# balancing_robot_h_bridges_power_sup.net
KiCad netlist of a schematic drawn in EAGLE
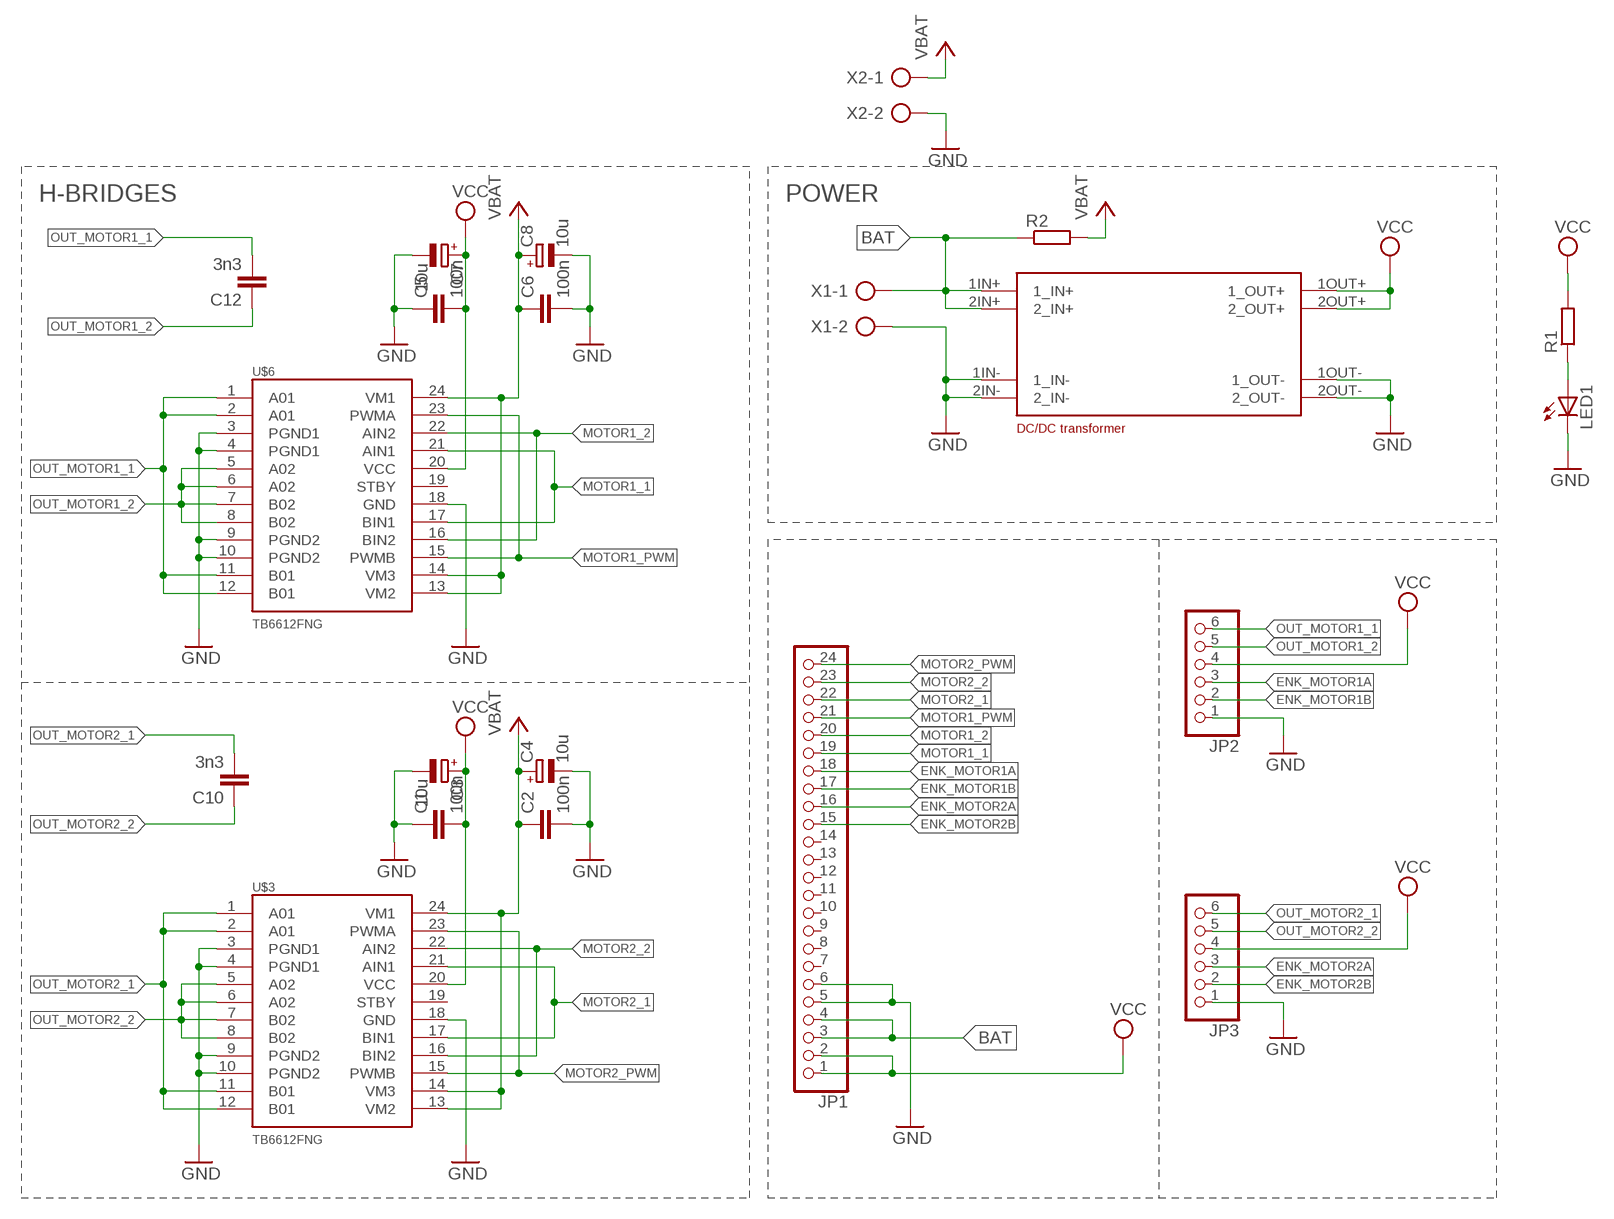
[diagram p0: schematic, sheet 1]

(export (version "E")
  (design (tool "Eeschema 10.0.6"))
  (components
    (comp (ref "C1")
      (value "100n")
      (footprint "eagle-import:C0603")
      (libsource (lib "eagle-import") (part "C-EUC0603"))
    )
    (comp (ref "C2")
      (value "100n")
      (footprint "eagle-import:C0603")
      (libsource (lib "eagle-import") (part "C-EUC0603"))
    )
    (comp (ref "C3")
      (value "10u")
      (footprint "eagle-import:153CLV-0405")
      (libsource (lib "eagle-import") (part "CPOL-EU153CLV-0405"))
    )
    (comp (ref "C4")
      (value "10u")
      (footprint "eagle-import:153CLV-0405")
      (libsource (lib "eagle-import") (part "CPOL-EU153CLV-0405"))
    )
    (comp (ref "C5")
      (value "100n")
      (footprint "eagle-import:C0603")
      (libsource (lib "eagle-import") (part "C-EUC0603"))
    )
    (comp (ref "C6")
      (value "100n")
      (footprint "eagle-import:C0603")
      (libsource (lib "eagle-import") (part "C-EUC0603"))
    )
    (comp (ref "C7")
      (value "10u")
      (footprint "eagle-import:153CLV-0405")
      (libsource (lib "eagle-import") (part "CPOL-EU153CLV-0405"))
    )
    (comp (ref "C8")
      (value "10u")
      (footprint "eagle-import:153CLV-0405")
      (libsource (lib "eagle-import") (part "CPOL-EU153CLV-0405"))
    )
    (comp (ref "C10")
      (value "3n3")
      (footprint "eagle-import:C0603")
      (libsource (lib "eagle-import") (part "C-EUC0603"))
    )
    (comp (ref "C12")
      (value "3n3")
      (footprint "eagle-import:C0603")
      (libsource (lib "eagle-import") (part "C-EUC0603"))
    )
    (comp (ref "JP1")
      (value "PINHD-1X24")
      (footprint "eagle-import:1X24")
      (libsource (lib "eagle-import") (part "PINHD-1X24"))
    )
    (comp (ref "JP2")
      (value "PINHD-1X6")
      (footprint "eagle-import:1X06")
      (libsource (lib "eagle-import") (part "PINHD-1X6"))
    )
    (comp (ref "JP3")
      (value "PINHD-1X6")
      (footprint "eagle-import:1X06")
      (libsource (lib "eagle-import") (part "PINHD-1X6"))
    )
    (comp (ref "LED1")
      (value "LEDCHIP-LED0603")
      (footprint "eagle-import:CHIP-LED0603")
      (libsource (lib "eagle-import") (part "LEDCHIP-LED0603"))
    )
    (comp (ref "R1")
      (value "R-EU_R0603")
      (footprint "eagle-import:R0603")
      (libsource (lib "eagle-import") (part "R-EU_R0603"))
    )
    (comp (ref "R2")
      (value "R-EU_R0805")
      (footprint "eagle-import:R0805")
      (libsource (lib "eagle-import") (part "R-EU_R0805"))
    )
    (comp (ref "U$3")
      (value "TB6612FNG")
      (footprint "eagle-import:SSOP24")
      (libsource (lib "eagle-import") (part "TB6612FNG"))
    )
    (comp (ref "U$4")
      (value "TRANSFORMER")
      (footprint "eagle-import:TRANSFORMER")
      (libsource (lib "eagle-import") (part "TRANSFORMER"))
    )
    (comp (ref "U$6")
      (value "TB6612FNG")
      (footprint "eagle-import:SSOP24")
      (libsource (lib "eagle-import") (part "TB6612FNG"))
    )
    (comp (ref "X1")
      (value "AK500/2")
      (footprint "eagle-import:AK500_2")
      (libsource (lib "eagle-import") (part "AK500/2"))
    )
    (comp (ref "X2")
      (value "AK500/2")
      (footprint "eagle-import:AK500_2")
      (libsource (lib "eagle-import") (part "AK500/2"))
    )
  )
  (nets
    (net (code "1") (name "BAT") (class "Default")
      (node (ref "JP1") (pin "3") (pinfunction "3_3") (pintype "passive"))
      (node (ref "JP1") (pin "4") (pinfunction "4_4") (pintype "passive"))
      (node (ref "R2") (pin "1") (pinfunction "1_1") (pintype "passive"))
      (node (ref "U$4") (pin "1IN+") (pinfunction "1_IN+_1IN+") (pintype "bidirectional"))
      (node (ref "U$4") (pin "2IN+") (pinfunction "2_IN+_2IN+") (pintype "bidirectional"))
      (node (ref "X1") (pin "1") (pinfunction "KL_1") (pintype "passive"))
    )
    (net (code "2") (name "ENK_MOTOR1A") (class "Default")
      (node (ref "JP1") (pin "18") (pinfunction "18_18") (pintype "passive"))
      (node (ref "JP2") (pin "3") (pinfunction "3_3") (pintype "passive"))
    )
    (net (code "3") (name "ENK_MOTOR1B") (class "Default")
      (node (ref "JP1") (pin "17") (pinfunction "17_17") (pintype "passive"))
      (node (ref "JP2") (pin "2") (pinfunction "2_2") (pintype "passive"))
    )
    (net (code "4") (name "ENK_MOTOR2A") (class "Default")
      (node (ref "JP1") (pin "16") (pinfunction "16_16") (pintype "passive"))
      (node (ref "JP3") (pin "3") (pinfunction "3_3") (pintype "passive"))
    )
    (net (code "5") (name "ENK_MOTOR2B") (class "Default")
      (node (ref "JP1") (pin "15") (pinfunction "15_15") (pintype "passive"))
      (node (ref "JP3") (pin "2") (pinfunction "2_2") (pintype "passive"))
    )
    (net (code "6") (name "GND") (class "Default")
      (node (ref "C1") (pin "1") (pinfunction "1_1") (pintype "passive"))
      (node (ref "C2") (pin "2") (pinfunction "2_2") (pintype "passive"))
      (node (ref "C3") (pin "-") (pinfunction "-_-") (pintype "passive"))
      (node (ref "C4") (pin "-") (pinfunction "-_-") (pintype "passive"))
      (node (ref "C5") (pin "1") (pinfunction "1_1") (pintype "passive"))
      (node (ref "C6") (pin "2") (pinfunction "2_2") (pintype "passive"))
      (node (ref "C7") (pin "-") (pinfunction "-_-") (pintype "passive"))
      (node (ref "C8") (pin "-") (pinfunction "-_-") (pintype "passive"))
      (node (ref "JP1") (pin "5") (pinfunction "5_5") (pintype "passive"))
      (node (ref "JP1") (pin "6") (pinfunction "6_6") (pintype "passive"))
      (node (ref "JP2") (pin "1") (pinfunction "1_1") (pintype "passive"))
      (node (ref "JP3") (pin "1") (pinfunction "1_1") (pintype "passive"))
      (node (ref "LED1") (pin "C") (pinfunction "C_C") (pintype "passive"))
      (node (ref "U$3") (pin "10") (pinfunction "PGND2_10") (pintype "bidirectional"))
      (node (ref "U$3") (pin "18") (pinfunction "GND_18") (pintype "bidirectional"))
      (node (ref "U$3") (pin "3") (pinfunction "PGND1_3") (pintype "bidirectional"))
      (node (ref "U$3") (pin "4") (pinfunction "PGND1_4") (pintype "bidirectional"))
      (node (ref "U$3") (pin "9") (pinfunction "PGND2_9") (pintype "bidirectional"))
      (node (ref "U$4") (pin "1IN-") (pinfunction "1_IN-_1IN-") (pintype "bidirectional"))
      (node (ref "U$4") (pin "1OUT-") (pinfunction "1_OUT-_1OUT-") (pintype "bidirectional"))
      (node (ref "U$4") (pin "2IN-") (pinfunction "2_IN-_2IN-") (pintype "bidirectional"))
      (node (ref "U$4") (pin "2OUT-") (pinfunction "2_OUT-_2OUT-") (pintype "bidirectional"))
      (node (ref "U$6") (pin "10") (pinfunction "PGND2_10") (pintype "bidirectional"))
      (node (ref "U$6") (pin "18") (pinfunction "GND_18") (pintype "bidirectional"))
      (node (ref "U$6") (pin "3") (pinfunction "PGND1_3") (pintype "bidirectional"))
      (node (ref "U$6") (pin "4") (pinfunction "PGND1_4") (pintype "bidirectional"))
      (node (ref "U$6") (pin "9") (pinfunction "PGND2_9") (pintype "bidirectional"))
      (node (ref "X1") (pin "2") (pinfunction "KL_2") (pintype "passive"))
      (node (ref "X2") (pin "2") (pinfunction "KL_2") (pintype "passive"))
    )
    (net (code "7") (name "MOTOR1_1") (class "Default")
      (node (ref "JP1") (pin "19") (pinfunction "19_19") (pintype "passive"))
      (node (ref "U$6") (pin "17") (pinfunction "BIN1_17") (pintype "bidirectional"))
      (node (ref "U$6") (pin "21") (pinfunction "AIN1_21") (pintype "bidirectional"))
    )
    (net (code "8") (name "MOTOR1_2") (class "Default")
      (node (ref "JP1") (pin "20") (pinfunction "20_20") (pintype "passive"))
      (node (ref "U$6") (pin "16") (pinfunction "BIN2_16") (pintype "bidirectional"))
      (node (ref "U$6") (pin "22") (pinfunction "AIN2_22") (pintype "bidirectional"))
    )
    (net (code "9") (name "MOTOR1_PWM") (class "Default")
      (node (ref "JP1") (pin "21") (pinfunction "21_21") (pintype "passive"))
      (node (ref "U$6") (pin "15") (pinfunction "PWMB_15") (pintype "bidirectional"))
      (node (ref "U$6") (pin "23") (pinfunction "PWMA_23") (pintype "bidirectional"))
    )
    (net (code "10") (name "MOTOR2_1") (class "Default")
      (node (ref "JP1") (pin "22") (pinfunction "22_22") (pintype "passive"))
      (node (ref "U$3") (pin "17") (pinfunction "BIN1_17") (pintype "bidirectional"))
      (node (ref "U$3") (pin "21") (pinfunction "AIN1_21") (pintype "bidirectional"))
    )
    (net (code "11") (name "MOTOR2_2") (class "Default")
      (node (ref "JP1") (pin "23") (pinfunction "23_23") (pintype "passive"))
      (node (ref "U$3") (pin "16") (pinfunction "BIN2_16") (pintype "bidirectional"))
      (node (ref "U$3") (pin "22") (pinfunction "AIN2_22") (pintype "bidirectional"))
    )
    (net (code "12") (name "MOTOR2_PWM") (class "Default")
      (node (ref "JP1") (pin "24") (pinfunction "24_24") (pintype "passive"))
      (node (ref "U$3") (pin "15") (pinfunction "PWMB_15") (pintype "bidirectional"))
      (node (ref "U$3") (pin "23") (pinfunction "PWMA_23") (pintype "bidirectional"))
    )
    (net (code "13") (name "Net-(LED1-PadA)") (class "Default")
      (node (ref "LED1") (pin "A") (pinfunction "A_A") (pintype "passive"))
      (node (ref "R1") (pin "1") (pinfunction "1_1") (pintype "passive"))
    )
    (net (code "14") (name "OUT_MOTOR1_1") (class "Default")
      (node (ref "C12") (pin "2") (pinfunction "2_2") (pintype "passive"))
      (node (ref "JP2") (pin "6") (pinfunction "6_6") (pintype "passive"))
      (node (ref "U$6") (pin "1") (pinfunction "A01_1") (pintype "bidirectional"))
      (node (ref "U$6") (pin "11") (pinfunction "B01_11") (pintype "bidirectional"))
      (node (ref "U$6") (pin "12") (pinfunction "B01_12") (pintype "bidirectional"))
      (node (ref "U$6") (pin "2") (pinfunction "A01_2") (pintype "bidirectional"))
    )
    (net (code "15") (name "OUT_MOTOR1_2") (class "Default")
      (node (ref "C12") (pin "1") (pinfunction "1_1") (pintype "passive"))
      (node (ref "JP2") (pin "5") (pinfunction "5_5") (pintype "passive"))
      (node (ref "U$6") (pin "5") (pinfunction "A02_5") (pintype "bidirectional"))
      (node (ref "U$6") (pin "6") (pinfunction "A02_6") (pintype "bidirectional"))
      (node (ref "U$6") (pin "7") (pinfunction "B02_7") (pintype "bidirectional"))
      (node (ref "U$6") (pin "8") (pinfunction "B02_8") (pintype "bidirectional"))
    )
    (net (code "16") (name "OUT_MOTOR2_1") (class "Default")
      (node (ref "C10") (pin "2") (pinfunction "2_2") (pintype "passive"))
      (node (ref "JP3") (pin "6") (pinfunction "6_6") (pintype "passive"))
      (node (ref "U$3") (pin "1") (pinfunction "A01_1") (pintype "bidirectional"))
      (node (ref "U$3") (pin "11") (pinfunction "B01_11") (pintype "bidirectional"))
      (node (ref "U$3") (pin "12") (pinfunction "B01_12") (pintype "bidirectional"))
      (node (ref "U$3") (pin "2") (pinfunction "A01_2") (pintype "bidirectional"))
    )
    (net (code "17") (name "OUT_MOTOR2_2") (class "Default")
      (node (ref "C10") (pin "1") (pinfunction "1_1") (pintype "passive"))
      (node (ref "JP3") (pin "5") (pinfunction "5_5") (pintype "passive"))
      (node (ref "U$3") (pin "5") (pinfunction "A02_5") (pintype "bidirectional"))
      (node (ref "U$3") (pin "6") (pinfunction "A02_6") (pintype "bidirectional"))
      (node (ref "U$3") (pin "7") (pinfunction "B02_7") (pintype "bidirectional"))
      (node (ref "U$3") (pin "8") (pinfunction "B02_8") (pintype "bidirectional"))
    )
    (net (code "18") (name "VBAT") (class "Default")
      (node (ref "C1") (pin "2") (pinfunction "2_2") (pintype "passive"))
      (node (ref "C2") (pin "1") (pinfunction "1_1") (pintype "passive"))
      (node (ref "C3") (pin "+") (pinfunction "+_+") (pintype "passive"))
      (node (ref "C4") (pin "+") (pinfunction "+_+") (pintype "passive"))
      (node (ref "C5") (pin "2") (pinfunction "2_2") (pintype "passive"))
      (node (ref "C6") (pin "1") (pinfunction "1_1") (pintype "passive"))
      (node (ref "C7") (pin "+") (pinfunction "+_+") (pintype "passive"))
      (node (ref "C8") (pin "+") (pinfunction "+_+") (pintype "passive"))
      (node (ref "JP1") (pin "1") (pinfunction "1_1") (pintype "passive"))
      (node (ref "JP1") (pin "2") (pinfunction "2_2") (pintype "passive"))
      (node (ref "JP2") (pin "4") (pinfunction "4_4") (pintype "passive"))
      (node (ref "JP3") (pin "4") (pinfunction "4_4") (pintype "passive"))
      (node (ref "R1") (pin "2") (pinfunction "2_2") (pintype "passive"))
      (node (ref "R2") (pin "2") (pinfunction "2_2") (pintype "passive"))
      (node (ref "U$3") (pin "13") (pinfunction "VM2_13") (pintype "bidirectional"))
      (node (ref "U$3") (pin "14") (pinfunction "VM3_14") (pintype "bidirectional"))
      (node (ref "U$3") (pin "20") (pinfunction "VCC_20") (pintype "bidirectional"))
      (node (ref "U$3") (pin "24") (pinfunction "VM1_24") (pintype "bidirectional"))
      (node (ref "U$4") (pin "1OUT+") (pinfunction "1_OUT+_1OUT+") (pintype "bidirectional"))
      (node (ref "U$4") (pin "2OUT+") (pinfunction "2_OUT+_2OUT+") (pintype "bidirectional"))
      (node (ref "U$6") (pin "13") (pinfunction "VM2_13") (pintype "bidirectional"))
      (node (ref "U$6") (pin "14") (pinfunction "VM3_14") (pintype "bidirectional"))
      (node (ref "U$6") (pin "20") (pinfunction "VCC_20") (pintype "bidirectional"))
      (node (ref "U$6") (pin "24") (pinfunction "VM1_24") (pintype "bidirectional"))
      (node (ref "X2") (pin "1") (pinfunction "KL_1") (pintype "passive"))
    )
    (net (code "19") (name "unconnected-(JP1-Pad7)") (class "Default")
      (node (ref "JP1") (pin "7") (pinfunction "7_7") (pintype "passive"))
    )
    (net (code "20") (name "unconnected-(JP1-Pad8)") (class "Default")
      (node (ref "JP1") (pin "8") (pinfunction "8_8") (pintype "passive"))
    )
    (net (code "21") (name "unconnected-(JP1-Pad9)") (class "Default")
      (node (ref "JP1") (pin "9") (pinfunction "9_9") (pintype "passive"))
    )
    (net (code "22") (name "unconnected-(JP1-Pad10)") (class "Default")
      (node (ref "JP1") (pin "10") (pinfunction "10_10") (pintype "passive"))
    )
    (net (code "23") (name "unconnected-(JP1-Pad11)") (class "Default")
      (node (ref "JP1") (pin "11") (pinfunction "11_11") (pintype "passive"))
    )
    (net (code "24") (name "unconnected-(JP1-Pad12)") (class "Default")
      (node (ref "JP1") (pin "12") (pinfunction "12_12") (pintype "passive"))
    )
    (net (code "25") (name "unconnected-(JP1-Pad13)") (class "Default")
      (node (ref "JP1") (pin "13") (pinfunction "13_13") (pintype "passive"))
    )
    (net (code "26") (name "unconnected-(JP1-Pad14)") (class "Default")
      (node (ref "JP1") (pin "14") (pinfunction "14_14") (pintype "passive"))
    )
    (net (code "27") (name "unconnected-(U$3-STBY-Pad19)") (class "Default")
      (node (ref "U$3") (pin "19") (pinfunction "STBY_19") (pintype "bidirectional"))
    )
    (net (code "28") (name "unconnected-(U$6-STBY-Pad19)") (class "Default")
      (node (ref "U$6") (pin "19") (pinfunction "STBY_19") (pintype "bidirectional"))
    )
  )
)
